# MR_BUS_BOARD.net
KiCad netlist of a schematic drawn in EAGLE
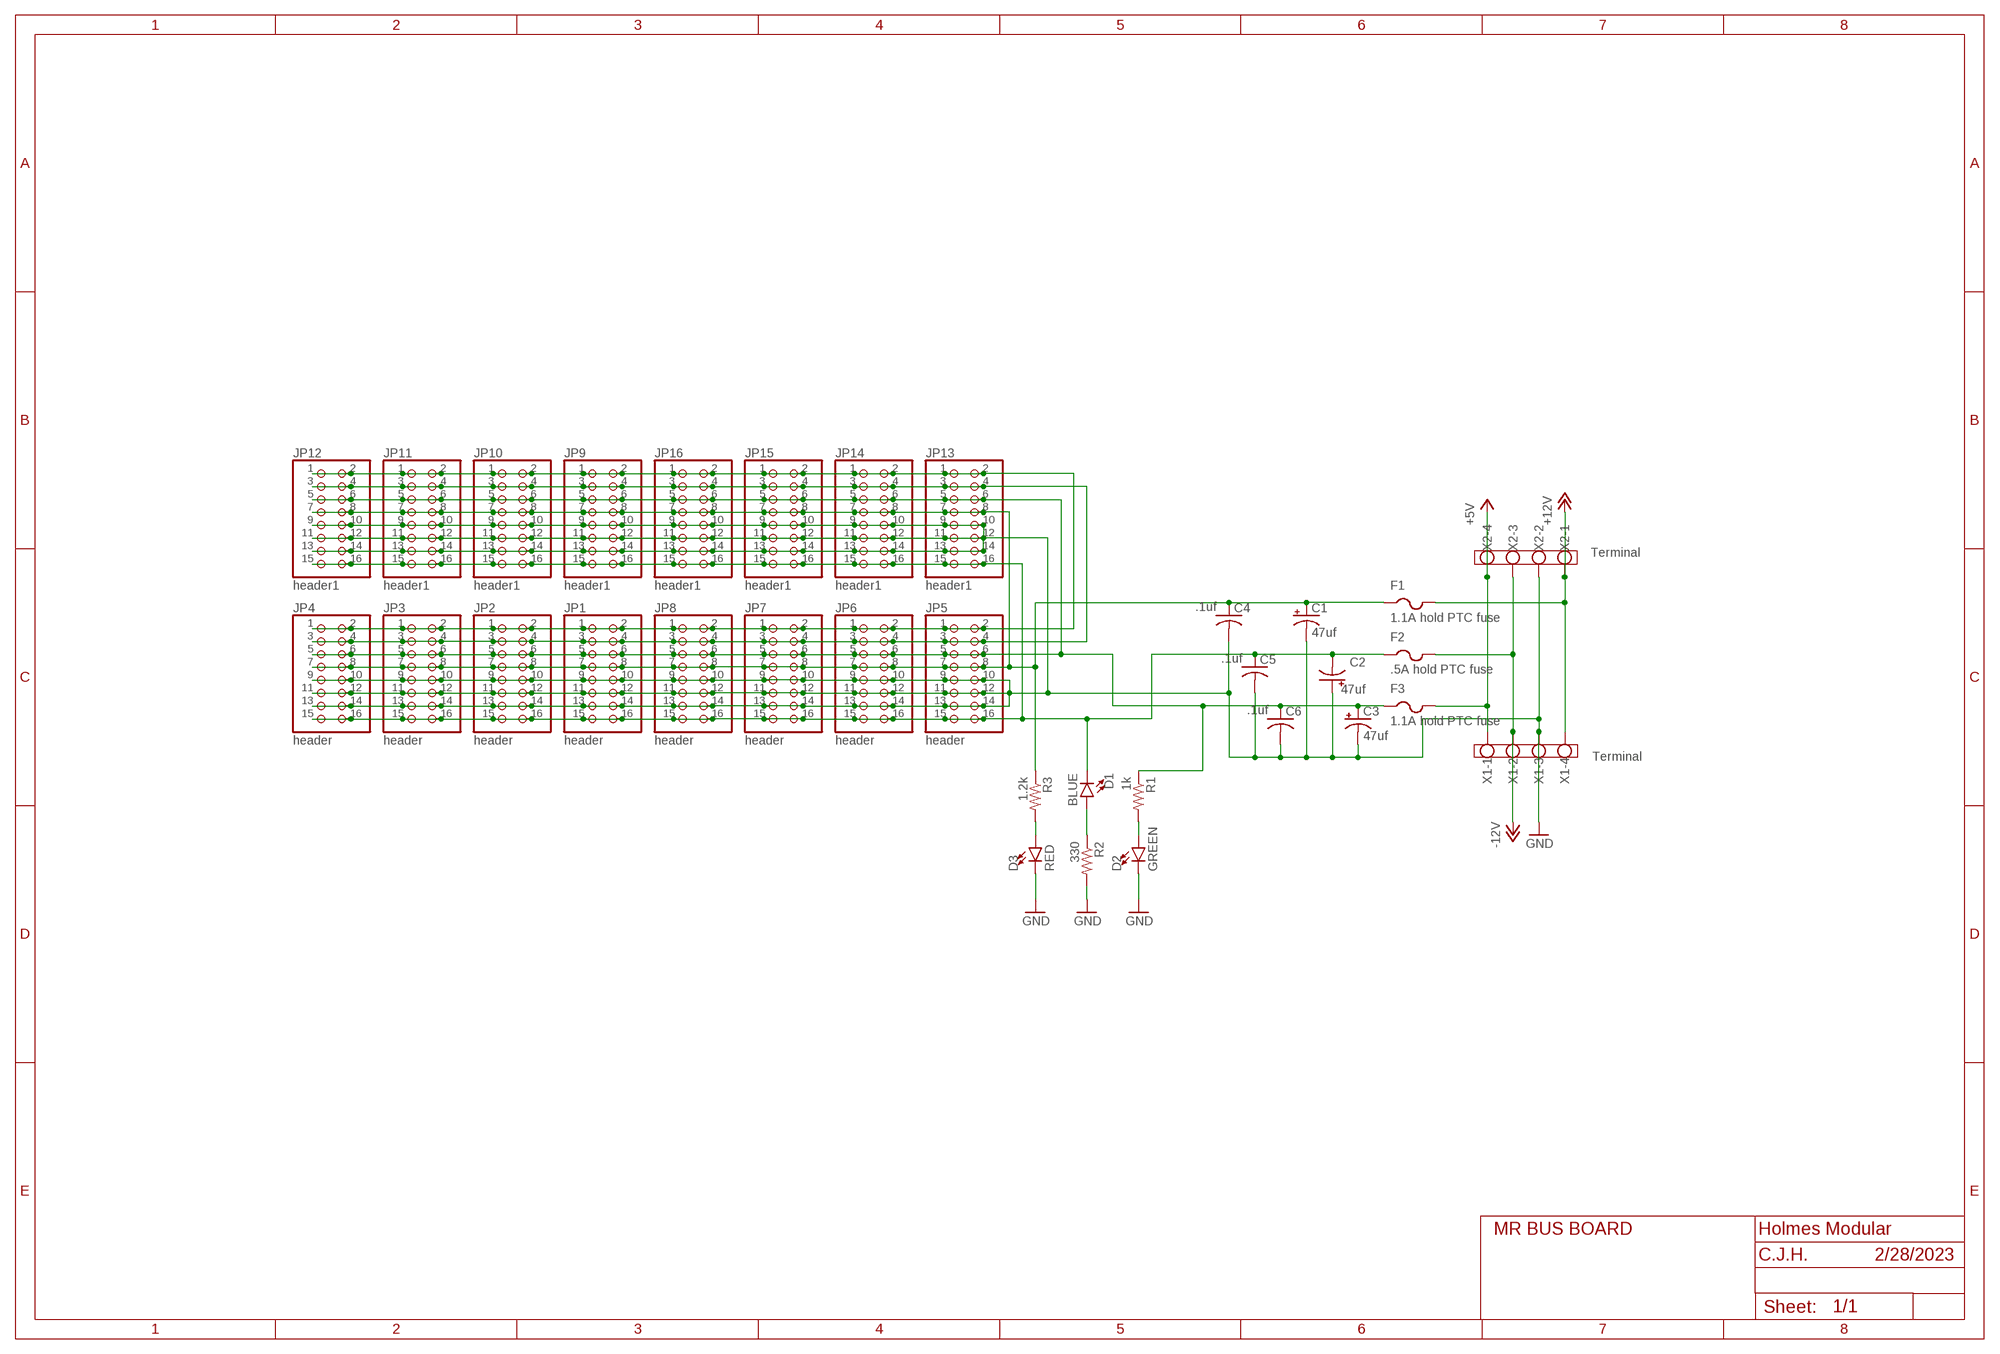
[diagram p0: schematic, sheet 1]

(export (version "E")
  (design (tool "Eeschema 10.0.6"))
  (components
    (comp (ref "C1")
      (value "47uf")
      (footprint "eagle-import:PANASONIC_D")
      (libsource (lib "eagle-import") (part "CPOL-USD"))
    )
    (comp (ref "C2")
      (value "47uf")
      (footprint "eagle-import:PANASONIC_D")
      (libsource (lib "eagle-import") (part "CPOL-USD"))
    )
    (comp (ref "C3")
      (value "47uf")
      (footprint "eagle-import:PANASONIC_D")
      (libsource (lib "eagle-import") (part "CPOL-USD"))
    )
    (comp (ref "C4")
      (value ".1uf")
      (footprint "eagle-import:C0805K")
      (libsource (lib "eagle-import") (part "C-USC0805K"))
    )
    (comp (ref "C5")
      (value ".1uf")
      (footprint "eagle-import:C0805K")
      (libsource (lib "eagle-import") (part "C-USC0805K"))
    )
    (comp (ref "C6")
      (value ".1uf")
      (footprint "eagle-import:C0805K")
      (libsource (lib "eagle-import") (part "C-USC0805K"))
    )
    (comp (ref "D1")
      (value "BLUE")
      (footprint "eagle-import:LED-0603")
      (libsource (lib "eagle-import") (part "LED-BLUE0603"))
    )
    (comp (ref "D2")
      (value "GREEN")
      (footprint "eagle-import:LED-0603")
      (libsource (lib "eagle-import") (part "LED-GREEN0603"))
    )
    (comp (ref "D3")
      (value "RED")
      (footprint "eagle-import:LED-0603")
      (libsource (lib "eagle-import") (part "LED-RED0603"))
    )
    (comp (ref "F1")
      (value "1.1A hold PTC fuse")
      (footprint "eagle-import:1812")
      (libsource (lib "eagle-import") (part "PTCFUSE-1812"))
    )
    (comp (ref "F2")
      (value ".5A hold PTC fuse")
      (footprint "eagle-import:1812")
      (libsource (lib "eagle-import") (part "PTCFUSE-1812"))
    )
    (comp (ref "F3")
      (value "1.1A hold PTC fuse")
      (footprint "eagle-import:1812")
      (libsource (lib "eagle-import") (part "PTCFUSE-1812"))
    )
    (comp (ref "JP1")
      (value "header")
      (footprint "eagle-import:2X08_SMT")
      (libsource (lib "eagle-import") (part "PINHD-2X8SMT"))
    )
    (comp (ref "JP2")
      (value "header")
      (footprint "eagle-import:2X08_SMT")
      (libsource (lib "eagle-import") (part "PINHD-2X8SMT"))
    )
    (comp (ref "JP3")
      (value "header")
      (footprint "eagle-import:2X08_SMT")
      (libsource (lib "eagle-import") (part "PINHD-2X8SMT"))
    )
    (comp (ref "JP4")
      (value "header")
      (footprint "eagle-import:2X08_SMT")
      (libsource (lib "eagle-import") (part "PINHD-2X8SMT"))
    )
    (comp (ref "JP5")
      (value "header")
      (footprint "eagle-import:2X08_SMT")
      (libsource (lib "eagle-import") (part "PINHD-2X8SMT"))
    )
    (comp (ref "JP6")
      (value "header")
      (footprint "eagle-import:2X08_SMT")
      (libsource (lib "eagle-import") (part "PINHD-2X8SMT"))
    )
    (comp (ref "JP7")
      (value "header")
      (footprint "eagle-import:2X08_SMT")
      (libsource (lib "eagle-import") (part "PINHD-2X8SMT"))
    )
    (comp (ref "JP8")
      (value "header")
      (footprint "eagle-import:2X08_SMT")
      (libsource (lib "eagle-import") (part "PINHD-2X8SMT"))
    )
    (comp (ref "JP9")
      (value "header1")
      (footprint "eagle-import:2X08")
      (libsource (lib "eagle-import") (part "PINHD-2X8"))
    )
    (comp (ref "JP10")
      (value "header1")
      (footprint "eagle-import:2X08")
      (libsource (lib "eagle-import") (part "PINHD-2X8"))
    )
    (comp (ref "JP11")
      (value "header1")
      (footprint "eagle-import:2X08")
      (libsource (lib "eagle-import") (part "PINHD-2X8"))
    )
    (comp (ref "JP12")
      (value "header1")
      (footprint "eagle-import:2X08")
      (libsource (lib "eagle-import") (part "PINHD-2X8"))
    )
    (comp (ref "JP13")
      (value "header1")
      (footprint "eagle-import:2X08")
      (libsource (lib "eagle-import") (part "PINHD-2X8"))
    )
    (comp (ref "JP14")
      (value "header1")
      (footprint "eagle-import:2X08")
      (libsource (lib "eagle-import") (part "PINHD-2X8"))
    )
    (comp (ref "JP15")
      (value "header1")
      (footprint "eagle-import:2X08")
      (libsource (lib "eagle-import") (part "PINHD-2X8"))
    )
    (comp (ref "JP16")
      (value "header1")
      (footprint "eagle-import:2X08")
      (libsource (lib "eagle-import") (part "PINHD-2X8"))
    )
    (comp (ref "R1")
      (value "1k")
      (footprint "eagle-import:R0805")
      (libsource (lib "eagle-import") (part "R-US_R0805"))
    )
    (comp (ref "R2")
      (value "330")
      (footprint "eagle-import:R0805")
      (libsource (lib "eagle-import") (part "R-US_R0805"))
    )
    (comp (ref "R3")
      (value "1.2k")
      (footprint "eagle-import:R0805")
      (libsource (lib "eagle-import") (part "R-US_R0805"))
    )
    (comp (ref "X1")
      (value "Terminal")
      (footprint "eagle-import:W237-4")
      (libsource (lib "eagle-import") (part "W237-4"))
    )
    (comp (ref "X2")
      (value "Terminal")
      (footprint "eagle-import:W237-4")
      (libsource (lib "eagle-import") (part "W237-4"))
    )
  )
  (nets
    (net (code "1") (name "+5V") (class "Default")
      (node (ref "F3") (pin "2") (pinfunction "2_2") (pintype "passive"))
      (node (ref "X1") (pin "1") (pinfunction "KL_1") (pintype "passive"))
      (node (ref "X2") (pin "4") (pinfunction "KL_4") (pintype "passive"))
    )
    (net (code "2") (name "+12V") (class "Default")
      (node (ref "F1") (pin "2") (pinfunction "2_2") (pintype "passive"))
      (node (ref "X1") (pin "4") (pinfunction "KL_4") (pintype "passive"))
      (node (ref "X2") (pin "1") (pinfunction "KL_1") (pintype "passive"))
    )
    (net (code "3") (name "-12V") (class "Default")
      (node (ref "F2") (pin "2") (pinfunction "2_2") (pintype "passive"))
      (node (ref "X1") (pin "2") (pinfunction "KL_2") (pintype "passive"))
      (node (ref "X2") (pin "3") (pinfunction "KL_3") (pintype "passive"))
    )
    (net (code "4") (name "GND") (class "Default")
      (node (ref "C1") (pin "-") (pinfunction "-_-") (pintype "passive"))
      (node (ref "C2") (pin "+") (pinfunction "+_+") (pintype "passive"))
      (node (ref "C3") (pin "-") (pinfunction "-_-") (pintype "passive"))
      (node (ref "C4") (pin "2") (pinfunction "2_2") (pintype "passive"))
      (node (ref "C5") (pin "2") (pinfunction "2_2") (pintype "passive"))
      (node (ref "C6") (pin "2") (pinfunction "2_2") (pintype "passive"))
      (node (ref "D2") (pin "C") (pinfunction "C_C") (pintype "passive"))
      (node (ref "D3") (pin "C") (pinfunction "C_C") (pintype "passive"))
      (node (ref "JP1") (pin "10") (pinfunction "10_10") (pintype "passive"))
      (node (ref "JP1") (pin "11") (pinfunction "11_11") (pintype "passive"))
      (node (ref "JP1") (pin "12") (pinfunction "12_12") (pintype "passive"))
      (node (ref "JP1") (pin "13") (pinfunction "13_13") (pintype "passive"))
      (node (ref "JP1") (pin "14") (pinfunction "14_14") (pintype "passive"))
      (node (ref "JP1") (pin "9") (pinfunction "9_9") (pintype "passive"))
      (node (ref "JP10") (pin "10") (pinfunction "10_10") (pintype "passive"))
      (node (ref "JP10") (pin "11") (pinfunction "11_11") (pintype "passive"))
      (node (ref "JP10") (pin "12") (pinfunction "12_12") (pintype "passive"))
      (node (ref "JP10") (pin "13") (pinfunction "13_13") (pintype "passive"))
      (node (ref "JP10") (pin "14") (pinfunction "14_14") (pintype "passive"))
      (node (ref "JP10") (pin "9") (pinfunction "9_9") (pintype "passive"))
      (node (ref "JP11") (pin "10") (pinfunction "10_10") (pintype "passive"))
      (node (ref "JP11") (pin "11") (pinfunction "11_11") (pintype "passive"))
      (node (ref "JP11") (pin "12") (pinfunction "12_12") (pintype "passive"))
      (node (ref "JP11") (pin "13") (pinfunction "13_13") (pintype "passive"))
      (node (ref "JP11") (pin "14") (pinfunction "14_14") (pintype "passive"))
      (node (ref "JP11") (pin "9") (pinfunction "9_9") (pintype "passive"))
      (node (ref "JP12") (pin "10") (pinfunction "10_10") (pintype "passive"))
      (node (ref "JP12") (pin "11") (pinfunction "11_11") (pintype "passive"))
      (node (ref "JP12") (pin "12") (pinfunction "12_12") (pintype "passive"))
      (node (ref "JP12") (pin "13") (pinfunction "13_13") (pintype "passive"))
      (node (ref "JP12") (pin "14") (pinfunction "14_14") (pintype "passive"))
      (node (ref "JP12") (pin "9") (pinfunction "9_9") (pintype "passive"))
      (node (ref "JP13") (pin "10") (pinfunction "10_10") (pintype "passive"))
      (node (ref "JP13") (pin "11") (pinfunction "11_11") (pintype "passive"))
      (node (ref "JP13") (pin "12") (pinfunction "12_12") (pintype "passive"))
      (node (ref "JP13") (pin "13") (pinfunction "13_13") (pintype "passive"))
      (node (ref "JP13") (pin "14") (pinfunction "14_14") (pintype "passive"))
      (node (ref "JP13") (pin "9") (pinfunction "9_9") (pintype "passive"))
      (node (ref "JP14") (pin "10") (pinfunction "10_10") (pintype "passive"))
      (node (ref "JP14") (pin "11") (pinfunction "11_11") (pintype "passive"))
      (node (ref "JP14") (pin "12") (pinfunction "12_12") (pintype "passive"))
      (node (ref "JP14") (pin "13") (pinfunction "13_13") (pintype "passive"))
      (node (ref "JP14") (pin "14") (pinfunction "14_14") (pintype "passive"))
      (node (ref "JP14") (pin "9") (pinfunction "9_9") (pintype "passive"))
      (node (ref "JP15") (pin "10") (pinfunction "10_10") (pintype "passive"))
      (node (ref "JP15") (pin "11") (pinfunction "11_11") (pintype "passive"))
      (node (ref "JP15") (pin "12") (pinfunction "12_12") (pintype "passive"))
      (node (ref "JP15") (pin "13") (pinfunction "13_13") (pintype "passive"))
      (node (ref "JP15") (pin "14") (pinfunction "14_14") (pintype "passive"))
      (node (ref "JP15") (pin "9") (pinfunction "9_9") (pintype "passive"))
      (node (ref "JP16") (pin "10") (pinfunction "10_10") (pintype "passive"))
      (node (ref "JP16") (pin "11") (pinfunction "11_11") (pintype "passive"))
      (node (ref "JP16") (pin "12") (pinfunction "12_12") (pintype "passive"))
      (node (ref "JP16") (pin "13") (pinfunction "13_13") (pintype "passive"))
      (node (ref "JP16") (pin "14") (pinfunction "14_14") (pintype "passive"))
      (node (ref "JP16") (pin "9") (pinfunction "9_9") (pintype "passive"))
      (node (ref "JP2") (pin "10") (pinfunction "10_10") (pintype "passive"))
      (node (ref "JP2") (pin "11") (pinfunction "11_11") (pintype "passive"))
      (node (ref "JP2") (pin "12") (pinfunction "12_12") (pintype "passive"))
      (node (ref "JP2") (pin "13") (pinfunction "13_13") (pintype "passive"))
      (node (ref "JP2") (pin "14") (pinfunction "14_14") (pintype "passive"))
      (node (ref "JP2") (pin "9") (pinfunction "9_9") (pintype "passive"))
      (node (ref "JP3") (pin "10") (pinfunction "10_10") (pintype "passive"))
      (node (ref "JP3") (pin "11") (pinfunction "11_11") (pintype "passive"))
      (node (ref "JP3") (pin "12") (pinfunction "12_12") (pintype "passive"))
      (node (ref "JP3") (pin "13") (pinfunction "13_13") (pintype "passive"))
      (node (ref "JP3") (pin "14") (pinfunction "14_14") (pintype "passive"))
      (node (ref "JP3") (pin "9") (pinfunction "9_9") (pintype "passive"))
      (node (ref "JP4") (pin "10") (pinfunction "10_10") (pintype "passive"))
      (node (ref "JP4") (pin "11") (pinfunction "11_11") (pintype "passive"))
      (node (ref "JP4") (pin "12") (pinfunction "12_12") (pintype "passive"))
      (node (ref "JP4") (pin "13") (pinfunction "13_13") (pintype "passive"))
      (node (ref "JP4") (pin "14") (pinfunction "14_14") (pintype "passive"))
      (node (ref "JP4") (pin "9") (pinfunction "9_9") (pintype "passive"))
      (node (ref "JP5") (pin "10") (pinfunction "10_10") (pintype "passive"))
      (node (ref "JP5") (pin "11") (pinfunction "11_11") (pintype "passive"))
      (node (ref "JP5") (pin "12") (pinfunction "12_12") (pintype "passive"))
      (node (ref "JP5") (pin "13") (pinfunction "13_13") (pintype "passive"))
      (node (ref "JP5") (pin "14") (pinfunction "14_14") (pintype "passive"))
      (node (ref "JP5") (pin "9") (pinfunction "9_9") (pintype "passive"))
      (node (ref "JP6") (pin "10") (pinfunction "10_10") (pintype "passive"))
      (node (ref "JP6") (pin "11") (pinfunction "11_11") (pintype "passive"))
      (node (ref "JP6") (pin "12") (pinfunction "12_12") (pintype "passive"))
      (node (ref "JP6") (pin "13") (pinfunction "13_13") (pintype "passive"))
      (node (ref "JP6") (pin "14") (pinfunction "14_14") (pintype "passive"))
      (node (ref "JP6") (pin "9") (pinfunction "9_9") (pintype "passive"))
      (node (ref "JP7") (pin "10") (pinfunction "10_10") (pintype "passive"))
      (node (ref "JP7") (pin "11") (pinfunction "11_11") (pintype "passive"))
      (node (ref "JP7") (pin "12") (pinfunction "12_12") (pintype "passive"))
      (node (ref "JP7") (pin "13") (pinfunction "13_13") (pintype "passive"))
      (node (ref "JP7") (pin "14") (pinfunction "14_14") (pintype "passive"))
      (node (ref "JP7") (pin "9") (pinfunction "9_9") (pintype "passive"))
      (node (ref "JP8") (pin "10") (pinfunction "10_10") (pintype "passive"))
      (node (ref "JP8") (pin "11") (pinfunction "11_11") (pintype "passive"))
      (node (ref "JP8") (pin "12") (pinfunction "12_12") (pintype "passive"))
      (node (ref "JP8") (pin "13") (pinfunction "13_13") (pintype "passive"))
      (node (ref "JP8") (pin "14") (pinfunction "14_14") (pintype "passive"))
      (node (ref "JP8") (pin "9") (pinfunction "9_9") (pintype "passive"))
      (node (ref "JP9") (pin "10") (pinfunction "10_10") (pintype "passive"))
      (node (ref "JP9") (pin "11") (pinfunction "11_11") (pintype "passive"))
      (node (ref "JP9") (pin "12") (pinfunction "12_12") (pintype "passive"))
      (node (ref "JP9") (pin "13") (pinfunction "13_13") (pintype "passive"))
      (node (ref "JP9") (pin "14") (pinfunction "14_14") (pintype "passive"))
      (node (ref "JP9") (pin "9") (pinfunction "9_9") (pintype "passive"))
      (node (ref "R2") (pin "2") (pinfunction "2_2") (pintype "passive"))
      (node (ref "X1") (pin "3") (pinfunction "KL_3") (pintype "passive"))
      (node (ref "X2") (pin "2") (pinfunction "KL_2") (pintype "passive"))
    )
    (net (code "5") (name "Net-(C1-Pad+)") (class "Default")
      (node (ref "C1") (pin "+") (pinfunction "+_+") (pintype "passive"))
      (node (ref "C4") (pin "1") (pinfunction "1_1") (pintype "passive"))
      (node (ref "F1") (pin "1") (pinfunction "1_1") (pintype "passive"))
      (node (ref "JP1") (pin "7") (pinfunction "7_7") (pintype "passive"))
      (node (ref "JP1") (pin "8") (pinfunction "8_8") (pintype "passive"))
      (node (ref "JP10") (pin "7") (pinfunction "7_7") (pintype "passive"))
      (node (ref "JP10") (pin "8") (pinfunction "8_8") (pintype "passive"))
      (node (ref "JP11") (pin "7") (pinfunction "7_7") (pintype "passive"))
      (node (ref "JP11") (pin "8") (pinfunction "8_8") (pintype "passive"))
      (node (ref "JP12") (pin "7") (pinfunction "7_7") (pintype "passive"))
      (node (ref "JP12") (pin "8") (pinfunction "8_8") (pintype "passive"))
      (node (ref "JP13") (pin "7") (pinfunction "7_7") (pintype "passive"))
      (node (ref "JP13") (pin "8") (pinfunction "8_8") (pintype "passive"))
      (node (ref "JP14") (pin "7") (pinfunction "7_7") (pintype "passive"))
      (node (ref "JP14") (pin "8") (pinfunction "8_8") (pintype "passive"))
      (node (ref "JP15") (pin "7") (pinfunction "7_7") (pintype "passive"))
      (node (ref "JP15") (pin "8") (pinfunction "8_8") (pintype "passive"))
      (node (ref "JP16") (pin "7") (pinfunction "7_7") (pintype "passive"))
      (node (ref "JP16") (pin "8") (pinfunction "8_8") (pintype "passive"))
      (node (ref "JP2") (pin "7") (pinfunction "7_7") (pintype "passive"))
      (node (ref "JP2") (pin "8") (pinfunction "8_8") (pintype "passive"))
      (node (ref "JP3") (pin "7") (pinfunction "7_7") (pintype "passive"))
      (node (ref "JP3") (pin "8") (pinfunction "8_8") (pintype "passive"))
      (node (ref "JP4") (pin "7") (pinfunction "7_7") (pintype "passive"))
      (node (ref "JP4") (pin "8") (pinfunction "8_8") (pintype "passive"))
      (node (ref "JP5") (pin "7") (pinfunction "7_7") (pintype "passive"))
      (node (ref "JP5") (pin "8") (pinfunction "8_8") (pintype "passive"))
      (node (ref "JP6") (pin "7") (pinfunction "7_7") (pintype "passive"))
      (node (ref "JP6") (pin "8") (pinfunction "8_8") (pintype "passive"))
      (node (ref "JP7") (pin "7") (pinfunction "7_7") (pintype "passive"))
      (node (ref "JP7") (pin "8") (pinfunction "8_8") (pintype "passive"))
      (node (ref "JP8") (pin "7") (pinfunction "7_7") (pintype "passive"))
      (node (ref "JP8") (pin "8") (pinfunction "8_8") (pintype "passive"))
      (node (ref "JP9") (pin "7") (pinfunction "7_7") (pintype "passive"))
      (node (ref "JP9") (pin "8") (pinfunction "8_8") (pintype "passive"))
      (node (ref "R3") (pin "1") (pinfunction "1_1") (pintype "passive"))
    )
    (net (code "6") (name "Net-(C2-Pad-)") (class "Default")
      (node (ref "C2") (pin "-") (pinfunction "-_-") (pintype "passive"))
      (node (ref "C5") (pin "1") (pinfunction "1_1") (pintype "passive"))
      (node (ref "D1") (pin "C") (pinfunction "C_C") (pintype "passive"))
      (node (ref "F2") (pin "1") (pinfunction "1_1") (pintype "passive"))
      (node (ref "JP1") (pin "15") (pinfunction "15_15") (pintype "passive"))
      (node (ref "JP1") (pin "16") (pinfunction "16_16") (pintype "passive"))
      (node (ref "JP10") (pin "15") (pinfunction "15_15") (pintype "passive"))
      (node (ref "JP10") (pin "16") (pinfunction "16_16") (pintype "passive"))
      (node (ref "JP11") (pin "15") (pinfunction "15_15") (pintype "passive"))
      (node (ref "JP11") (pin "16") (pinfunction "16_16") (pintype "passive"))
      (node (ref "JP12") (pin "15") (pinfunction "15_15") (pintype "passive"))
      (node (ref "JP12") (pin "16") (pinfunction "16_16") (pintype "passive"))
      (node (ref "JP13") (pin "15") (pinfunction "15_15") (pintype "passive"))
      (node (ref "JP13") (pin "16") (pinfunction "16_16") (pintype "passive"))
      (node (ref "JP14") (pin "15") (pinfunction "15_15") (pintype "passive"))
      (node (ref "JP14") (pin "16") (pinfunction "16_16") (pintype "passive"))
      (node (ref "JP15") (pin "15") (pinfunction "15_15") (pintype "passive"))
      (node (ref "JP15") (pin "16") (pinfunction "16_16") (pintype "passive"))
      (node (ref "JP16") (pin "15") (pinfunction "15_15") (pintype "passive"))
      (node (ref "JP16") (pin "16") (pinfunction "16_16") (pintype "passive"))
      (node (ref "JP2") (pin "15") (pinfunction "15_15") (pintype "passive"))
      (node (ref "JP2") (pin "16") (pinfunction "16_16") (pintype "passive"))
      (node (ref "JP3") (pin "15") (pinfunction "15_15") (pintype "passive"))
      (node (ref "JP3") (pin "16") (pinfunction "16_16") (pintype "passive"))
      (node (ref "JP4") (pin "15") (pinfunction "15_15") (pintype "passive"))
      (node (ref "JP4") (pin "16") (pinfunction "16_16") (pintype "passive"))
      (node (ref "JP5") (pin "15") (pinfunction "15_15") (pintype "passive"))
      (node (ref "JP5") (pin "16") (pinfunction "16_16") (pintype "passive"))
      (node (ref "JP6") (pin "15") (pinfunction "15_15") (pintype "passive"))
      (node (ref "JP6") (pin "16") (pinfunction "16_16") (pintype "passive"))
      (node (ref "JP7") (pin "15") (pinfunction "15_15") (pintype "passive"))
      (node (ref "JP7") (pin "16") (pinfunction "16_16") (pintype "passive"))
      (node (ref "JP8") (pin "15") (pinfunction "15_15") (pintype "passive"))
      (node (ref "JP8") (pin "16") (pinfunction "16_16") (pintype "passive"))
      (node (ref "JP9") (pin "15") (pinfunction "15_15") (pintype "passive"))
      (node (ref "JP9") (pin "16") (pinfunction "16_16") (pintype "passive"))
    )
    (net (code "7") (name "Net-(C3-Pad+)") (class "Default")
      (node (ref "C3") (pin "+") (pinfunction "+_+") (pintype "passive"))
      (node (ref "C6") (pin "1") (pinfunction "1_1") (pintype "passive"))
      (node (ref "F3") (pin "1") (pinfunction "1_1") (pintype "passive"))
      (node (ref "JP1") (pin "5") (pinfunction "5_5") (pintype "passive"))
      (node (ref "JP1") (pin "6") (pinfunction "6_6") (pintype "passive"))
      (node (ref "JP10") (pin "5") (pinfunction "5_5") (pintype "passive"))
      (node (ref "JP10") (pin "6") (pinfunction "6_6") (pintype "passive"))
      (node (ref "JP11") (pin "5") (pinfunction "5_5") (pintype "passive"))
      (node (ref "JP11") (pin "6") (pinfunction "6_6") (pintype "passive"))
      (node (ref "JP12") (pin "5") (pinfunction "5_5") (pintype "passive"))
      (node (ref "JP12") (pin "6") (pinfunction "6_6") (pintype "passive"))
      (node (ref "JP13") (pin "5") (pinfunction "5_5") (pintype "passive"))
      (node (ref "JP13") (pin "6") (pinfunction "6_6") (pintype "passive"))
      (node (ref "JP14") (pin "5") (pinfunction "5_5") (pintype "passive"))
      (node (ref "JP14") (pin "6") (pinfunction "6_6") (pintype "passive"))
      (node (ref "JP15") (pin "5") (pinfunction "5_5") (pintype "passive"))
      (node (ref "JP15") (pin "6") (pinfunction "6_6") (pintype "passive"))
      (node (ref "JP16") (pin "5") (pinfunction "5_5") (pintype "passive"))
      (node (ref "JP16") (pin "6") (pinfunction "6_6") (pintype "passive"))
      (node (ref "JP2") (pin "5") (pinfunction "5_5") (pintype "passive"))
      (node (ref "JP2") (pin "6") (pinfunction "6_6") (pintype "passive"))
      (node (ref "JP3") (pin "5") (pinfunction "5_5") (pintype "passive"))
      (node (ref "JP3") (pin "6") (pinfunction "6_6") (pintype "passive"))
      (node (ref "JP4") (pin "5") (pinfunction "5_5") (pintype "passive"))
      (node (ref "JP4") (pin "6") (pinfunction "6_6") (pintype "passive"))
      (node (ref "JP5") (pin "5") (pinfunction "5_5") (pintype "passive"))
      (node (ref "JP5") (pin "6") (pinfunction "6_6") (pintype "passive"))
      (node (ref "JP6") (pin "5") (pinfunction "5_5") (pintype "passive"))
      (node (ref "JP6") (pin "6") (pinfunction "6_6") (pintype "passive"))
      (node (ref "JP7") (pin "5") (pinfunction "5_5") (pintype "passive"))
      (node (ref "JP7") (pin "6") (pinfunction "6_6") (pintype "passive"))
      (node (ref "JP8") (pin "5") (pinfunction "5_5") (pintype "passive"))
      (node (ref "JP8") (pin "6") (pinfunction "6_6") (pintype "passive"))
      (node (ref "JP9") (pin "5") (pinfunction "5_5") (pintype "passive"))
      (node (ref "JP9") (pin "6") (pinfunction "6_6") (pintype "passive"))
      (node (ref "R1") (pin "1") (pinfunction "1_1") (pintype "passive"))
    )
    (net (code "8") (name "Net-(D1-PadA)") (class "Default")
      (node (ref "D1") (pin "A") (pinfunction "A_A") (pintype "passive"))
      (node (ref "R2") (pin "1") (pinfunction "1_1") (pintype "passive"))
    )
    (net (code "9") (name "Net-(D2-PadA)") (class "Default")
      (node (ref "D2") (pin "A") (pinfunction "A_A") (pintype "passive"))
      (node (ref "R1") (pin "2") (pinfunction "2_2") (pintype "passive"))
    )
    (net (code "10") (name "Net-(D3-PadA)") (class "Default")
      (node (ref "D3") (pin "A") (pinfunction "A_A") (pintype "passive"))
      (node (ref "R3") (pin "2") (pinfunction "2_2") (pintype "passive"))
    )
    (net (code "11") (name "Net-(JP1-Pad1)") (class "Default")
      (node (ref "JP1") (pin "1") (pinfunction "1_1") (pintype "passive"))
      (node (ref "JP1") (pin "2") (pinfunction "2_2") (pintype "passive"))
      (node (ref "JP10") (pin "1") (pinfunction "1_1") (pintype "passive"))
      (node (ref "JP10") (pin "2") (pinfunction "2_2") (pintype "passive"))
      (node (ref "JP11") (pin "1") (pinfunction "1_1") (pintype "passive"))
      (node (ref "JP11") (pin "2") (pinfunction "2_2") (pintype "passive"))
      (node (ref "JP12") (pin "1") (pinfunction "1_1") (pintype "passive"))
      (node (ref "JP12") (pin "2") (pinfunction "2_2") (pintype "passive"))
      (node (ref "JP13") (pin "1") (pinfunction "1_1") (pintype "passive"))
      (node (ref "JP13") (pin "2") (pinfunction "2_2") (pintype "passive"))
      (node (ref "JP14") (pin "1") (pinfunction "1_1") (pintype "passive"))
      (node (ref "JP14") (pin "2") (pinfunction "2_2") (pintype "passive"))
      (node (ref "JP15") (pin "1") (pinfunction "1_1") (pintype "passive"))
      (node (ref "JP15") (pin "2") (pinfunction "2_2") (pintype "passive"))
      (node (ref "JP16") (pin "1") (pinfunction "1_1") (pintype "passive"))
      (node (ref "JP16") (pin "2") (pinfunction "2_2") (pintype "passive"))
      (node (ref "JP2") (pin "1") (pinfunction "1_1") (pintype "passive"))
      (node (ref "JP2") (pin "2") (pinfunction "2_2") (pintype "passive"))
      (node (ref "JP3") (pin "1") (pinfunction "1_1") (pintype "passive"))
      (node (ref "JP3") (pin "2") (pinfunction "2_2") (pintype "passive"))
      (node (ref "JP4") (pin "1") (pinfunction "1_1") (pintype "passive"))
      (node (ref "JP4") (pin "2") (pinfunction "2_2") (pintype "passive"))
      (node (ref "JP5") (pin "1") (pinfunction "1_1") (pintype "passive"))
      (node (ref "JP5") (pin "2") (pinfunction "2_2") (pintype "passive"))
      (node (ref "JP6") (pin "1") (pinfunction "1_1") (pintype "passive"))
      (node (ref "JP6") (pin "2") (pinfunction "2_2") (pintype "passive"))
      (node (ref "JP7") (pin "1") (pinfunction "1_1") (pintype "passive"))
      (node (ref "JP7") (pin "2") (pinfunction "2_2") (pintype "passive"))
      (node (ref "JP8") (pin "1") (pinfunction "1_1") (pintype "passive"))
      (node (ref "JP8") (pin "2") (pinfunction "2_2") (pintype "passive"))
      (node (ref "JP9") (pin "1") (pinfunction "1_1") (pintype "passive"))
      (node (ref "JP9") (pin "2") (pinfunction "2_2") (pintype "passive"))
    )
    (net (code "12") (name "Net-(JP1-Pad3)") (class "Default")
      (node (ref "JP1") (pin "3") (pinfunction "3_3") (pintype "passive"))
      (node (ref "JP1") (pin "4") (pinfunction "4_4") (pintype "passive"))
      (node (ref "JP10") (pin "3") (pinfunction "3_3") (pintype "passive"))
      (node (ref "JP10") (pin "4") (pinfunction "4_4") (pintype "passive"))
      (node (ref "JP11") (pin "3") (pinfunction "3_3") (pintype "passive"))
      (node (ref "JP11") (pin "4") (pinfunction "4_4") (pintype "passive"))
      (node (ref "JP12") (pin "3") (pinfunction "3_3") (pintype "passive"))
      (node (ref "JP12") (pin "4") (pinfunction "4_4") (pintype "passive"))
      (node (ref "JP13") (pin "3") (pinfunction "3_3") (pintype "passive"))
      (node (ref "JP13") (pin "4") (pinfunction "4_4") (pintype "passive"))
      (node (ref "JP14") (pin "3") (pinfunction "3_3") (pintype "passive"))
      (node (ref "JP14") (pin "4") (pinfunction "4_4") (pintype "passive"))
      (node (ref "JP15") (pin "3") (pinfunction "3_3") (pintype "passive"))
      (node (ref "JP15") (pin "4") (pinfunction "4_4") (pintype "passive"))
      (node (ref "JP16") (pin "3") (pinfunction "3_3") (pintype "passive"))
      (node (ref "JP16") (pin "4") (pinfunction "4_4") (pintype "passive"))
      (node (ref "JP2") (pin "3") (pinfunction "3_3") (pintype "passive"))
      (node (ref "JP2") (pin "4") (pinfunction "4_4") (pintype "passive"))
      (node (ref "JP3") (pin "3") (pinfunction "3_3") (pintype "passive"))
      (node (ref "JP3") (pin "4") (pinfunction "4_4") (pintype "passive"))
      (node (ref "JP4") (pin "3") (pinfunction "3_3") (pintype "passive"))
      (node (ref "JP4") (pin "4") (pinfunction "4_4") (pintype "passive"))
      (node (ref "JP5") (pin "3") (pinfunction "3_3") (pintype "passive"))
      (node (ref "JP5") (pin "4") (pinfunction "4_4") (pintype "passive"))
      (node (ref "JP6") (pin "3") (pinfunction "3_3") (pintype "passive"))
      (node (ref "JP6") (pin "4") (pinfunction "4_4") (pintype "passive"))
      (node (ref "JP7") (pin "3") (pinfunction "3_3") (pintype "passive"))
      (node (ref "JP7") (pin "4") (pinfunction "4_4") (pintype "passive"))
      (node (ref "JP8") (pin "3") (pinfunction "3_3") (pintype "passive"))
      (node (ref "JP8") (pin "4") (pinfunction "4_4") (pintype "passive"))
      (node (ref "JP9") (pin "3") (pinfunction "3_3") (pintype "passive"))
      (node (ref "JP9") (pin "4") (pinfunction "4_4") (pintype "passive"))
    )
  )
)
